# 08_USB_To_UART.net
KiCad netlist of a schematic drawn in Altium Designer
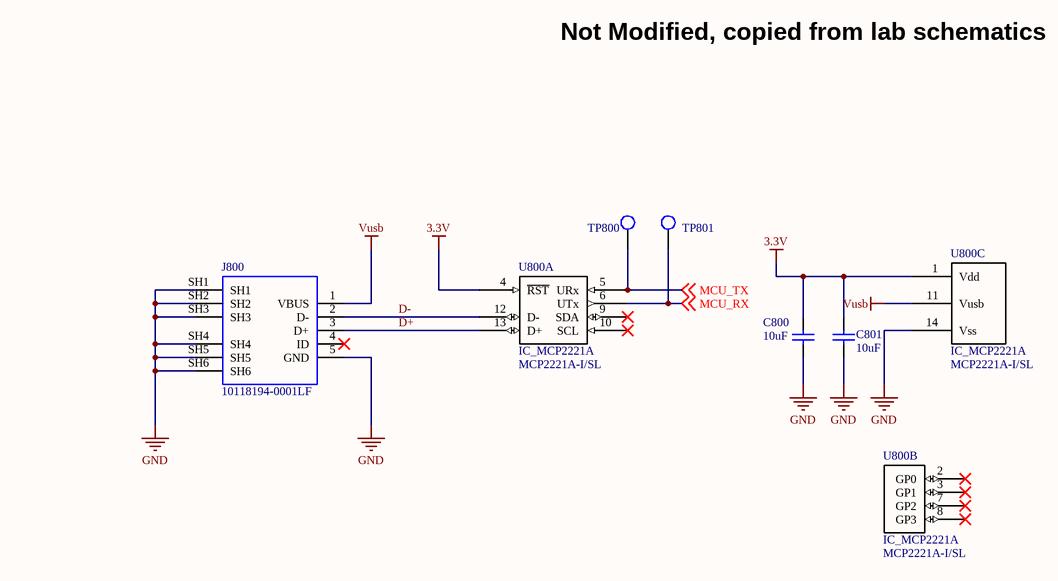
[diagram p0: 08_USB_To_UART.SchDoc]

(export (version "E")
  (design (tool "Eeschema 10.0.6"))
  (components
    (comp (ref "C800")
      (value "10uF")
      (footprint "CAP_0805")
      (description "CAP CER 10UF 16V X7R 0805")
      (fields
        (field (name "MANUFACTURER") "Samsung")
        (field (name "MANUFACTURER PART NUMBER") "CL21A106KPCLQNC")
        (field (name "CAPACITANCE") "10uF")
      )
      (libsource (lib "ece315-S20") (part "CAP_0805_U_010.00"))
    )
    (comp (ref "C801")
      (value "10uF")
      (footprint "CAP_0805")
      (description "CAP CER 10UF 16V X7R 0805")
      (fields
        (field (name "MANUFACTURER") "Samsung")
        (field (name "MANUFACTURER PART NUMBER") "CL21A106KPCLQNC")
        (field (name "CAPACITANCE") "10uF")
      )
      (libsource (lib "ece315-S20") (part "CAP_0805_U_010.00"))
    )
    (comp (ref "J800")
      (value "USB_MICRO_B_10118194-0001LF")
      (footprint "USB_MICRO_B")
      (description "CONN USB MICRO B RECPT SMT R/A")
      (fields
        (field (name "MANUFACTURER") "Amphenol FCI")
        (field (name "MANUFACTURER PART NUMBER") "10118194-0001LF")
      )
      (libsource (lib "ece315-S20") (part "USB_MICRO_B_10118194-0001LF"))
    )
    (comp (ref "TP800")
      (value "TP_1206")
      (footprint "TP-SMC-1206")
      (description "Test Point SMD 1206")
      (fields
        (field (name "MANUFACTURER") "TE Connectivity (Tyco Electronics)")
        (field (name "MANUFACTURER PART NUMBER") "1625854-1")
      )
      (libsource (lib "ece315-S20") (part "TP_1206"))
    )
    (comp (ref "TP801")
      (value "TP_1206")
      (footprint "TP-SMC-1206")
      (description "Test Point SMD 1206")
      (fields
        (field (name "MANUFACTURER") "TE Connectivity (Tyco Electronics)")
        (field (name "MANUFACTURER PART NUMBER") "1625854-1")
      )
      (libsource (lib "ece315-S20") (part "TP_1206"))
    )
    (comp (ref "U800")
      (value "IC_MCP2221A")
      (footprint "IC_MCP2221A")
      (description "IC USB TO I2C/UART 14SOIC")
      (fields
        (field (name "MANUFACTURER") "Microchip")
        (field (name "MANUFACTURER PART NUMBER") "MCP2221A-I/SL")
      )
      (libsource (lib "ece315-S20") (part "IC_MCP2221A"))
    )
  )
  (nets
    (net (code "1") (name "/D+") (class "Default")
      (node (ref "J800") (pin "3") (pinfunction "D+_3") (pintype "passive"))
      (node (ref "U800") (pin "13") (pinfunction "D+_13") (pintype "bidirectional"))
    )
    (net (code "2") (name "/D-") (class "Default")
      (node (ref "J800") (pin "2") (pinfunction "D-_2") (pintype "passive"))
      (node (ref "U800") (pin "12") (pinfunction "D-_12") (pintype "bidirectional"))
    )
    (net (code "3") (name "3.3V") (class "Default")
      (node (ref "C800") (pin "2") (pinfunction "2_2") (pintype "passive"))
      (node (ref "C801") (pin "2") (pinfunction "2_2") (pintype "passive"))
      (node (ref "U800") (pin "1") (pinfunction "Vdd_1") (pintype "power_in"))
      (node (ref "U800") (pin "4") (pinfunction "~{RST}_4") (pintype "input"))
    )
    (net (code "4") (name "GND") (class "Default")
      (node (ref "C800") (pin "1") (pinfunction "1_1") (pintype "passive"))
      (node (ref "C801") (pin "1") (pinfunction "1_1") (pintype "passive"))
      (node (ref "J800") (pin "5") (pinfunction "GND_5") (pintype "passive"))
      (node (ref "J800") (pin "SH1") (pinfunction "SH1_SH1") (pintype "passive"))
      (node (ref "J800") (pin "SH2") (pinfunction "SH2_SH2") (pintype "passive"))
      (node (ref "J800") (pin "SH3") (pinfunction "SH3_SH3") (pintype "passive"))
      (node (ref "J800") (pin "SH4") (pinfunction "SH4_SH4") (pintype "passive"))
      (node (ref "J800") (pin "SH5") (pinfunction "SH5_SH5") (pintype "passive"))
      (node (ref "J800") (pin "SH6") (pinfunction "SH6_SH6") (pintype "passive"))
      (node (ref "U800") (pin "14") (pinfunction "Vss_14") (pintype "power_in"))
    )
    (net (code "5") (name "MCU_RX") (class "Default")
      (node (ref "TP801") (pin "1") (pintype "passive"))
      (node (ref "U800") (pin "6") (pinfunction "UTx_6") (pintype "output"))
    )
    (net (code "6") (name "MCU_TX") (class "Default")
      (node (ref "TP800") (pin "1") (pintype "passive"))
      (node (ref "U800") (pin "5") (pinfunction "URx_5") (pintype "input"))
    )
    (net (code "7") (name "Vusb") (class "Default")
      (node (ref "J800") (pin "1") (pinfunction "VBUS_1") (pintype "passive"))
      (node (ref "U800") (pin "11") (pinfunction "Vusb_11") (pintype "power_in"))
    )
    (net (code "8") (name "unconnected-(J800-ID-Pad4)") (class "Default")
      (node (ref "J800") (pin "4") (pinfunction "ID_4") (pintype "passive+no_connect"))
    )
    (net (code "9") (name "unconnected-(U800A-SCL-Pad10)") (class "Default")
      (node (ref "U800") (pin "10") (pinfunction "SCL_10") (pintype "input+no_connect"))
    )
    (net (code "10") (name "unconnected-(U800A-SDA-Pad9)") (class "Default")
      (node (ref "U800") (pin "9") (pinfunction "SDA_9") (pintype "bidirectional+no_connect"))
    )
    (net (code "11") (name "unconnected-(U800B-GP0-Pad2)") (class "Default")
      (node (ref "U800") (pin "2") (pinfunction "GP0_2") (pintype "bidirectional+no_connect"))
    )
    (net (code "12") (name "unconnected-(U800B-GP1-Pad3)") (class "Default")
      (node (ref "U800") (pin "3") (pinfunction "GP1_3") (pintype "bidirectional+no_connect"))
    )
    (net (code "13") (name "unconnected-(U800B-GP2-Pad7)") (class "Default")
      (node (ref "U800") (pin "7") (pinfunction "GP2_7") (pintype "bidirectional+no_connect"))
    )
    (net (code "14") (name "unconnected-(U800B-GP3-Pad8)") (class "Default")
      (node (ref "U800") (pin "8") (pinfunction "GP3_8") (pintype "bidirectional+no_connect"))
    )
  )
)
